# LEDs.net
KiCad netlist of a schematic drawn in Altium Designer
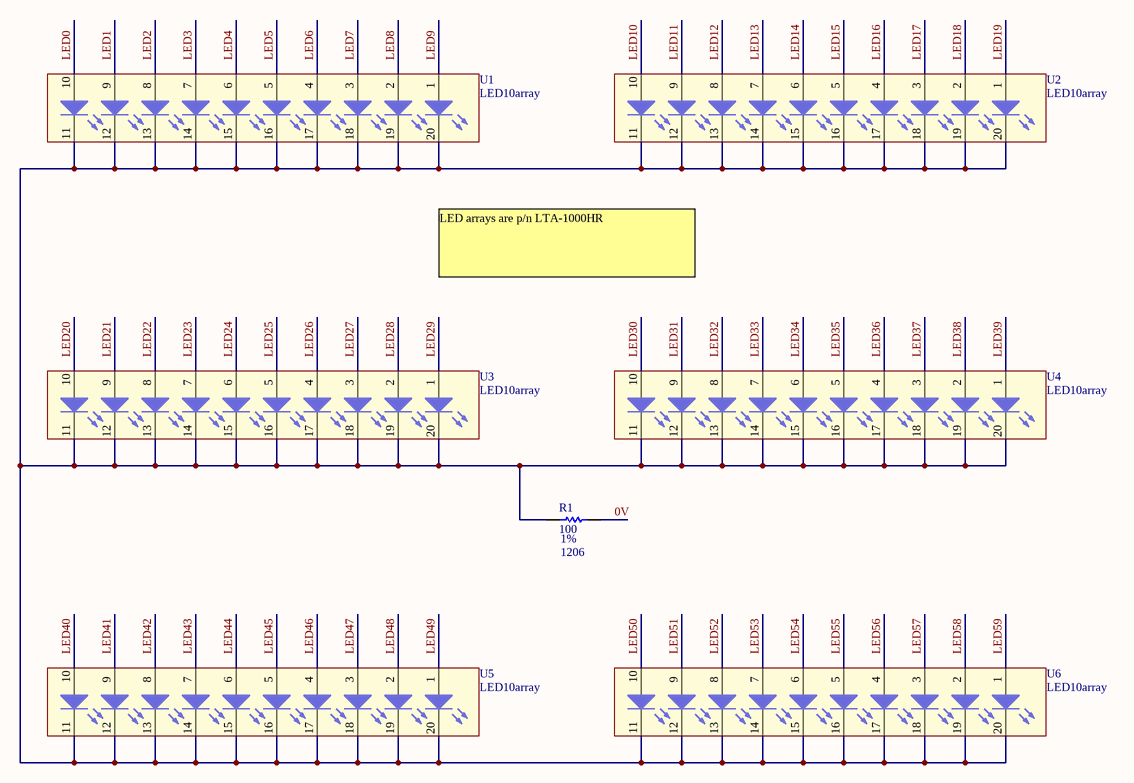
[diagram p0: LEDs.SchDoc]

(export (version "E")
  (design (tool "Eeschema 10.0.6"))
  (components
    (comp (ref "R1")
      (value "100")
      (footprint "1206")
      (description "Resistor")
      (fields (field (name "PARAM") "1%"))
      (libsource (lib "AdamsParts") (part "Res1206"))
    )
    (comp (ref "U1")
      (value "LED10array")
      (footprint "LED10array")
      (libsource (lib "AdamsParts") (part "LED10array"))
    )
    (comp (ref "U2")
      (value "LED10array")
      (footprint "LED10array")
      (libsource (lib "AdamsParts") (part "LED10array"))
    )
    (comp (ref "U3")
      (value "LED10array")
      (footprint "LED10array")
      (libsource (lib "AdamsParts") (part "LED10array"))
    )
    (comp (ref "U4")
      (value "LED10array")
      (footprint "LED10array")
      (libsource (lib "AdamsParts") (part "LED10array"))
    )
    (comp (ref "U5")
      (value "LED10array")
      (footprint "LED10array")
      (libsource (lib "AdamsParts") (part "LED10array"))
    )
    (comp (ref "U6")
      (value "LED10array")
      (footprint "LED10array")
      (libsource (lib "AdamsParts") (part "LED10array"))
    )
  )
  (nets
    (net (code "1") (name "/0V") (class "Default")
      (node (ref "R1") (pin "2") (pinfunction "2_2") (pintype "passive"))
    )
    (net (code "2") (name "/LED0") (class "Default")
      (node (ref "U1") (pin "10") (pinfunction "10_10") (pintype "passive"))
    )
    (net (code "3") (name "/LED1") (class "Default")
      (node (ref "U1") (pin "9") (pinfunction "9_9") (pintype "passive"))
    )
    (net (code "4") (name "/LED2") (class "Default")
      (node (ref "U1") (pin "8") (pinfunction "8_8") (pintype "passive"))
    )
    (net (code "5") (name "/LED3") (class "Default")
      (node (ref "U1") (pin "7") (pinfunction "7_7") (pintype "passive"))
    )
    (net (code "6") (name "/LED4") (class "Default")
      (node (ref "U1") (pin "6") (pinfunction "6_6") (pintype "passive"))
    )
    (net (code "7") (name "/LED5") (class "Default")
      (node (ref "U1") (pin "5") (pinfunction "5_5") (pintype "passive"))
    )
    (net (code "8") (name "/LED6") (class "Default")
      (node (ref "U1") (pin "4") (pinfunction "4_4") (pintype "passive"))
    )
    (net (code "9") (name "/LED7") (class "Default")
      (node (ref "U1") (pin "3") (pinfunction "3_3") (pintype "passive"))
    )
    (net (code "10") (name "/LED8") (class "Default")
      (node (ref "U1") (pin "2") (pinfunction "2_2") (pintype "passive"))
    )
    (net (code "11") (name "/LED9") (class "Default")
      (node (ref "U1") (pin "1") (pinfunction "1_1") (pintype "passive"))
    )
    (net (code "12") (name "/LED10") (class "Default")
      (node (ref "U2") (pin "10") (pinfunction "10_10") (pintype "passive"))
    )
    (net (code "13") (name "/LED11") (class "Default")
      (node (ref "U2") (pin "9") (pinfunction "9_9") (pintype "passive"))
    )
    (net (code "14") (name "/LED12") (class "Default")
      (node (ref "U2") (pin "8") (pinfunction "8_8") (pintype "passive"))
    )
    (net (code "15") (name "/LED13") (class "Default")
      (node (ref "U2") (pin "7") (pinfunction "7_7") (pintype "passive"))
    )
    (net (code "16") (name "/LED14") (class "Default")
      (node (ref "U2") (pin "6") (pinfunction "6_6") (pintype "passive"))
    )
    (net (code "17") (name "/LED15") (class "Default")
      (node (ref "U2") (pin "5") (pinfunction "5_5") (pintype "passive"))
    )
    (net (code "18") (name "/LED16") (class "Default")
      (node (ref "U2") (pin "4") (pinfunction "4_4") (pintype "passive"))
    )
    (net (code "19") (name "/LED17") (class "Default")
      (node (ref "U2") (pin "3") (pinfunction "3_3") (pintype "passive"))
    )
    (net (code "20") (name "/LED18") (class "Default")
      (node (ref "U2") (pin "2") (pinfunction "2_2") (pintype "passive"))
    )
    (net (code "21") (name "/LED19") (class "Default")
      (node (ref "U2") (pin "1") (pinfunction "1_1") (pintype "passive"))
    )
    (net (code "22") (name "/LED20") (class "Default")
      (node (ref "U3") (pin "10") (pinfunction "10_10") (pintype "passive"))
    )
    (net (code "23") (name "/LED21") (class "Default")
      (node (ref "U3") (pin "9") (pinfunction "9_9") (pintype "passive"))
    )
    (net (code "24") (name "/LED22") (class "Default")
      (node (ref "U3") (pin "8") (pinfunction "8_8") (pintype "passive"))
    )
    (net (code "25") (name "/LED23") (class "Default")
      (node (ref "U3") (pin "7") (pinfunction "7_7") (pintype "passive"))
    )
    (net (code "26") (name "/LED24") (class "Default")
      (node (ref "U3") (pin "6") (pinfunction "6_6") (pintype "passive"))
    )
    (net (code "27") (name "/LED25") (class "Default")
      (node (ref "U3") (pin "5") (pinfunction "5_5") (pintype "passive"))
    )
    (net (code "28") (name "/LED26") (class "Default")
      (node (ref "U3") (pin "4") (pinfunction "4_4") (pintype "passive"))
    )
    (net (code "29") (name "/LED27") (class "Default")
      (node (ref "U3") (pin "3") (pinfunction "3_3") (pintype "passive"))
    )
    (net (code "30") (name "/LED28") (class "Default")
      (node (ref "U3") (pin "2") (pinfunction "2_2") (pintype "passive"))
    )
    (net (code "31") (name "/LED29") (class "Default")
      (node (ref "U3") (pin "1") (pinfunction "1_1") (pintype "passive"))
    )
    (net (code "32") (name "/LED30") (class "Default")
      (node (ref "U4") (pin "10") (pinfunction "10_10") (pintype "passive"))
    )
    (net (code "33") (name "/LED31") (class "Default")
      (node (ref "U4") (pin "9") (pinfunction "9_9") (pintype "passive"))
    )
    (net (code "34") (name "/LED32") (class "Default")
      (node (ref "U4") (pin "8") (pinfunction "8_8") (pintype "passive"))
    )
    (net (code "35") (name "/LED33") (class "Default")
      (node (ref "U4") (pin "7") (pinfunction "7_7") (pintype "passive"))
    )
    (net (code "36") (name "/LED34") (class "Default")
      (node (ref "U4") (pin "6") (pinfunction "6_6") (pintype "passive"))
    )
    (net (code "37") (name "/LED35") (class "Default")
      (node (ref "U4") (pin "5") (pinfunction "5_5") (pintype "passive"))
    )
    (net (code "38") (name "/LED36") (class "Default")
      (node (ref "U4") (pin "4") (pinfunction "4_4") (pintype "passive"))
    )
    (net (code "39") (name "/LED37") (class "Default")
      (node (ref "U4") (pin "3") (pinfunction "3_3") (pintype "passive"))
    )
    (net (code "40") (name "/LED38") (class "Default")
      (node (ref "U4") (pin "2") (pinfunction "2_2") (pintype "passive"))
    )
    (net (code "41") (name "/LED39") (class "Default")
      (node (ref "U4") (pin "1") (pinfunction "1_1") (pintype "passive"))
    )
    (net (code "42") (name "/LED40") (class "Default")
      (node (ref "U5") (pin "10") (pinfunction "10_10") (pintype "passive"))
    )
    (net (code "43") (name "/LED41") (class "Default")
      (node (ref "U5") (pin "9") (pinfunction "9_9") (pintype "passive"))
    )
    (net (code "44") (name "/LED42") (class "Default")
      (node (ref "U5") (pin "8") (pinfunction "8_8") (pintype "passive"))
    )
    (net (code "45") (name "/LED43") (class "Default")
      (node (ref "U5") (pin "7") (pinfunction "7_7") (pintype "passive"))
    )
    (net (code "46") (name "/LED44") (class "Default")
      (node (ref "U5") (pin "6") (pinfunction "6_6") (pintype "passive"))
    )
    (net (code "47") (name "/LED45") (class "Default")
      (node (ref "U5") (pin "5") (pinfunction "5_5") (pintype "passive"))
    )
    (net (code "48") (name "/LED46") (class "Default")
      (node (ref "U5") (pin "4") (pinfunction "4_4") (pintype "passive"))
    )
    (net (code "49") (name "/LED47") (class "Default")
      (node (ref "U5") (pin "3") (pinfunction "3_3") (pintype "passive"))
    )
    (net (code "50") (name "/LED48") (class "Default")
      (node (ref "U5") (pin "2") (pinfunction "2_2") (pintype "passive"))
    )
    (net (code "51") (name "/LED49") (class "Default")
      (node (ref "U5") (pin "1") (pinfunction "1_1") (pintype "passive"))
    )
    (net (code "52") (name "/LED50") (class "Default")
      (node (ref "U6") (pin "10") (pinfunction "10_10") (pintype "passive"))
    )
    (net (code "53") (name "/LED51") (class "Default")
      (node (ref "U6") (pin "9") (pinfunction "9_9") (pintype "passive"))
    )
    (net (code "54") (name "/LED52") (class "Default")
      (node (ref "U6") (pin "8") (pinfunction "8_8") (pintype "passive"))
    )
    (net (code "55") (name "/LED53") (class "Default")
      (node (ref "U6") (pin "7") (pinfunction "7_7") (pintype "passive"))
    )
    (net (code "56") (name "/LED54") (class "Default")
      (node (ref "U6") (pin "6") (pinfunction "6_6") (pintype "passive"))
    )
    (net (code "57") (name "/LED55") (class "Default")
      (node (ref "U6") (pin "5") (pinfunction "5_5") (pintype "passive"))
    )
    (net (code "58") (name "/LED56") (class "Default")
      (node (ref "U6") (pin "4") (pinfunction "4_4") (pintype "passive"))
    )
    (net (code "59") (name "/LED57") (class "Default")
      (node (ref "U6") (pin "3") (pinfunction "3_3") (pintype "passive"))
    )
    (net (code "60") (name "/LED58") (class "Default")
      (node (ref "U6") (pin "2") (pinfunction "2_2") (pintype "passive"))
    )
    (net (code "61") (name "/LED59") (class "Default")
      (node (ref "U6") (pin "1") (pinfunction "1_1") (pintype "passive"))
    )
    (net (code "62") (name "Net-(R1-Pad1)") (class "Default")
      (node (ref "R1") (pin "1") (pinfunction "1_1") (pintype "passive"))
      (node (ref "U1") (pin "11") (pinfunction "11_11") (pintype "passive"))
      (node (ref "U1") (pin "12") (pinfunction "12_12") (pintype "passive"))
      (node (ref "U1") (pin "13") (pinfunction "13_13") (pintype "passive"))
      (node (ref "U1") (pin "14") (pinfunction "14_14") (pintype "passive"))
      (node (ref "U1") (pin "15") (pinfunction "15_15") (pintype "passive"))
      (node (ref "U1") (pin "16") (pinfunction "16_16") (pintype "passive"))
      (node (ref "U1") (pin "17") (pinfunction "17_17") (pintype "passive"))
      (node (ref "U1") (pin "18") (pinfunction "18_18") (pintype "passive"))
      (node (ref "U1") (pin "19") (pinfunction "19_19") (pintype "passive"))
      (node (ref "U1") (pin "20") (pinfunction "20_20") (pintype "passive"))
      (node (ref "U2") (pin "11") (pinfunction "11_11") (pintype "passive"))
      (node (ref "U2") (pin "12") (pinfunction "12_12") (pintype "passive"))
      (node (ref "U2") (pin "13") (pinfunction "13_13") (pintype "passive"))
      (node (ref "U2") (pin "14") (pinfunction "14_14") (pintype "passive"))
      (node (ref "U2") (pin "15") (pinfunction "15_15") (pintype "passive"))
      (node (ref "U2") (pin "16") (pinfunction "16_16") (pintype "passive"))
      (node (ref "U2") (pin "17") (pinfunction "17_17") (pintype "passive"))
      (node (ref "U2") (pin "18") (pinfunction "18_18") (pintype "passive"))
      (node (ref "U2") (pin "19") (pinfunction "19_19") (pintype "passive"))
      (node (ref "U2") (pin "20") (pinfunction "20_20") (pintype "passive"))
      (node (ref "U3") (pin "11") (pinfunction "11_11") (pintype "passive"))
      (node (ref "U3") (pin "12") (pinfunction "12_12") (pintype "passive"))
      (node (ref "U3") (pin "13") (pinfunction "13_13") (pintype "passive"))
      (node (ref "U3") (pin "14") (pinfunction "14_14") (pintype "passive"))
      (node (ref "U3") (pin "15") (pinfunction "15_15") (pintype "passive"))
      (node (ref "U3") (pin "16") (pinfunction "16_16") (pintype "passive"))
      (node (ref "U3") (pin "17") (pinfunction "17_17") (pintype "passive"))
      (node (ref "U3") (pin "18") (pinfunction "18_18") (pintype "passive"))
      (node (ref "U3") (pin "19") (pinfunction "19_19") (pintype "passive"))
      (node (ref "U3") (pin "20") (pinfunction "20_20") (pintype "passive"))
      (node (ref "U4") (pin "11") (pinfunction "11_11") (pintype "passive"))
      (node (ref "U4") (pin "12") (pinfunction "12_12") (pintype "passive"))
      (node (ref "U4") (pin "13") (pinfunction "13_13") (pintype "passive"))
      (node (ref "U4") (pin "14") (pinfunction "14_14") (pintype "passive"))
      (node (ref "U4") (pin "15") (pinfunction "15_15") (pintype "passive"))
      (node (ref "U4") (pin "16") (pinfunction "16_16") (pintype "passive"))
      (node (ref "U4") (pin "17") (pinfunction "17_17") (pintype "passive"))
      (node (ref "U4") (pin "18") (pinfunction "18_18") (pintype "passive"))
      (node (ref "U4") (pin "19") (pinfunction "19_19") (pintype "passive"))
      (node (ref "U4") (pin "20") (pinfunction "20_20") (pintype "passive"))
      (node (ref "U5") (pin "11") (pinfunction "11_11") (pintype "passive"))
      (node (ref "U5") (pin "12") (pinfunction "12_12") (pintype "passive"))
      (node (ref "U5") (pin "13") (pinfunction "13_13") (pintype "passive"))
      (node (ref "U5") (pin "14") (pinfunction "14_14") (pintype "passive"))
      (node (ref "U5") (pin "15") (pinfunction "15_15") (pintype "passive"))
      (node (ref "U5") (pin "16") (pinfunction "16_16") (pintype "passive"))
      (node (ref "U5") (pin "17") (pinfunction "17_17") (pintype "passive"))
      (node (ref "U5") (pin "18") (pinfunction "18_18") (pintype "passive"))
      (node (ref "U5") (pin "19") (pinfunction "19_19") (pintype "passive"))
      (node (ref "U5") (pin "20") (pinfunction "20_20") (pintype "passive"))
      (node (ref "U6") (pin "11") (pinfunction "11_11") (pintype "passive"))
      (node (ref "U6") (pin "12") (pinfunction "12_12") (pintype "passive"))
      (node (ref "U6") (pin "13") (pinfunction "13_13") (pintype "passive"))
      (node (ref "U6") (pin "14") (pinfunction "14_14") (pintype "passive"))
      (node (ref "U6") (pin "15") (pinfunction "15_15") (pintype "passive"))
      (node (ref "U6") (pin "16") (pinfunction "16_16") (pintype "passive"))
      (node (ref "U6") (pin "17") (pinfunction "17_17") (pintype "passive"))
      (node (ref "U6") (pin "18") (pinfunction "18_18") (pintype "passive"))
      (node (ref "U6") (pin "19") (pinfunction "19_19") (pintype "passive"))
      (node (ref "U6") (pin "20") (pinfunction "20_20") (pintype "passive"))
    )
  )
)
